# Sch6.net
KiCad netlist of a schematic drawn in EAGLE
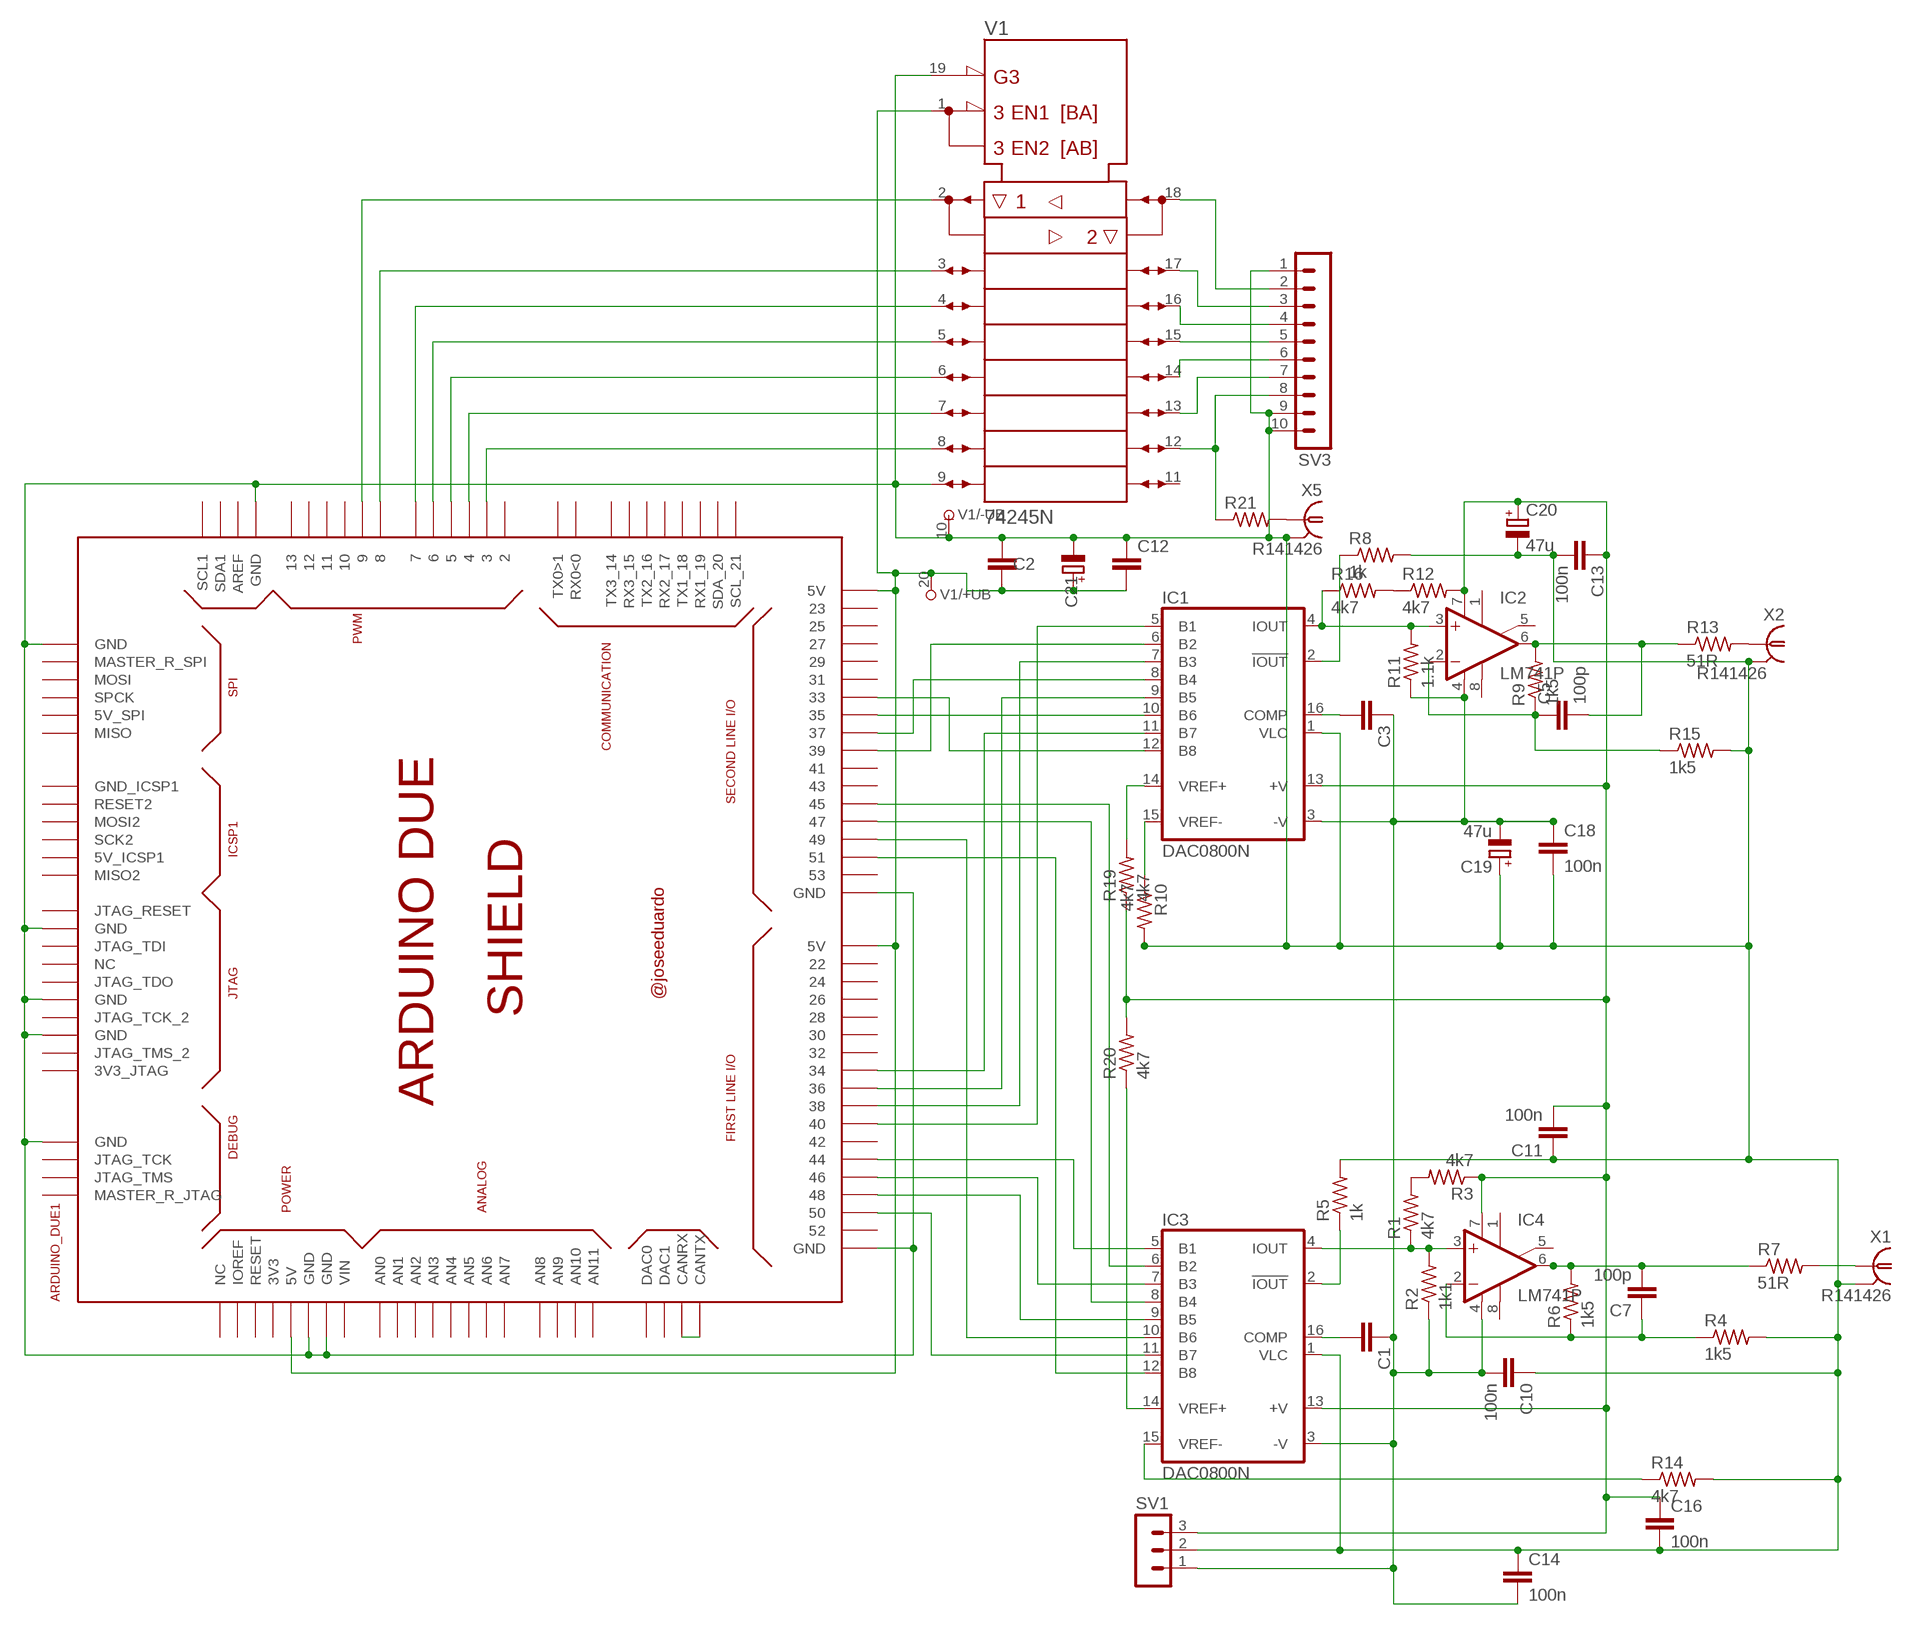
[diagram p0: schematic, sheet 1]

(export (version "E")
  (design (tool "Eeschema 10.0.6"))
  (components
    (comp (ref "ARDUINO_DUE1")
      (value "ARDUINO_DUE_SHIELD")
      (footprint "eagle-import:ARDUINO_DUE_SHIELD")
      (libsource (lib "eagle-import") (part "ARDUINO_DUE_SHIELD"))
    )
    (comp (ref "C1")
      (value "C-EU050-025X075")
      (footprint "eagle-import:C050-025X075")
      (libsource (lib "eagle-import") (part "C-EU050-025X075"))
    )
    (comp (ref "C2")
      (value "C-EU050-025X075")
      (footprint "eagle-import:C050-025X075")
      (libsource (lib "eagle-import") (part "C-EU050-025X075"))
    )
    (comp (ref "C3")
      (value "C-EU050-025X075")
      (footprint "eagle-import:C050-025X075")
      (libsource (lib "eagle-import") (part "C-EU050-025X075"))
    )
    (comp (ref "C5")
      (value "100p")
      (footprint "eagle-import:C050-025X075")
      (libsource (lib "eagle-import") (part "C-EU050-025X075"))
    )
    (comp (ref "C7")
      (value "100p")
      (footprint "eagle-import:C050-025X075")
      (libsource (lib "eagle-import") (part "C-EU050-025X075"))
    )
    (comp (ref "C10")
      (value "100n")
      (footprint "eagle-import:C050-025X075")
      (libsource (lib "eagle-import") (part "C-EU050-025X075"))
    )
    (comp (ref "C11")
      (value "100n")
      (footprint "eagle-import:C050-025X075")
      (libsource (lib "eagle-import") (part "C-EU050-025X075"))
    )
    (comp (ref "C12")
      (value "C-EU050-025X075")
      (footprint "eagle-import:C050-025X075")
      (libsource (lib "eagle-import") (part "C-EU050-025X075"))
    )
    (comp (ref "C13")
      (value "100n")
      (footprint "eagle-import:C050-025X075")
      (libsource (lib "eagle-import") (part "C-EU050-025X075"))
    )
    (comp (ref "C14")
      (value "100n")
      (footprint "eagle-import:C050-025X075")
      (libsource (lib "eagle-import") (part "C-EU050-025X075"))
    )
    (comp (ref "C16")
      (value "100n")
      (footprint "eagle-import:C050-025X075")
      (libsource (lib "eagle-import") (part "C-EU050-025X075"))
    )
    (comp (ref "C18")
      (value "100n")
      (footprint "eagle-import:C050-025X075")
      (libsource (lib "eagle-import") (part "C-EU050-025X075"))
    )
    (comp (ref "C19")
      (value "47u")
      (footprint "eagle-import:E5-10,5")
      (libsource (lib "eagle-import") (part "CPOL-EUE5-10.5"))
    )
    (comp (ref "C20")
      (value "47u")
      (footprint "eagle-import:E5-10,5")
      (libsource (lib "eagle-import") (part "CPOL-EUE5-10.5"))
    )
    (comp (ref "C21")
      (value "CPOL-EUE5-10.5")
      (footprint "eagle-import:E5-10,5")
      (libsource (lib "eagle-import") (part "CPOL-EUE5-10.5"))
    )
    (comp (ref "IC1")
      (value "DAC0800N")
      (footprint "eagle-import:DIL16")
      (libsource (lib "eagle-import") (part "DAC0800N"))
    )
    (comp (ref "IC2")
      (value "LM741P")
      (footprint "eagle-import:DIL08")
      (libsource (lib "eagle-import") (part "741PLM"))
    )
    (comp (ref "IC3")
      (value "DAC0800N")
      (footprint "eagle-import:DIL16")
      (libsource (lib "eagle-import") (part "DAC0800N"))
    )
    (comp (ref "IC4")
      (value "LM741P")
      (footprint "eagle-import:DIL08")
      (libsource (lib "eagle-import") (part "741PLM"))
    )
    (comp (ref "R1")
      (value "4k7")
      (footprint "eagle-import:0207_10")
      (libsource (lib "eagle-import") (part "R-US_0207/10"))
    )
    (comp (ref "R2")
      (value "1k1")
      (footprint "eagle-import:0207_10")
      (libsource (lib "eagle-import") (part "R-US_0207/10"))
    )
    (comp (ref "R3")
      (value "4k7")
      (footprint "eagle-import:0207_10")
      (libsource (lib "eagle-import") (part "R-US_0207/10"))
    )
    (comp (ref "R4")
      (value "1k5")
      (footprint "eagle-import:0207_10")
      (libsource (lib "eagle-import") (part "R-US_0207/10"))
    )
    (comp (ref "R5")
      (value "1k")
      (footprint "eagle-import:0207_10")
      (libsource (lib "eagle-import") (part "R-US_0207/10"))
    )
    (comp (ref "R6")
      (value "1k5")
      (footprint "eagle-import:0207_10")
      (libsource (lib "eagle-import") (part "R-US_0207/10"))
    )
    (comp (ref "R7")
      (value "51R")
      (footprint "eagle-import:0207_10")
      (libsource (lib "eagle-import") (part "R-US_0207/10"))
    )
    (comp (ref "R8")
      (value "1k")
      (footprint "eagle-import:0207_10")
      (libsource (lib "eagle-import") (part "R-US_0207/10"))
    )
    (comp (ref "R9")
      (value "1k5")
      (footprint "eagle-import:0207_10")
      (libsource (lib "eagle-import") (part "R-US_0207/10"))
    )
    (comp (ref "R10")
      (value "4k7")
      (footprint "eagle-import:0207_10")
      (libsource (lib "eagle-import") (part "R-US_0207/10"))
    )
    (comp (ref "R11")
      (value "1.1k")
      (footprint "eagle-import:0207_10")
      (libsource (lib "eagle-import") (part "R-US_0207/10"))
    )
    (comp (ref "R12")
      (value "4k7")
      (footprint "eagle-import:0207_10")
      (libsource (lib "eagle-import") (part "R-US_0207/10"))
    )
    (comp (ref "R13")
      (value "51R")
      (footprint "eagle-import:0207_10")
      (libsource (lib "eagle-import") (part "R-US_0207/10"))
    )
    (comp (ref "R14")
      (value "4k7")
      (footprint "eagle-import:0207_10")
      (libsource (lib "eagle-import") (part "R-US_0207/10"))
    )
    (comp (ref "R15")
      (value "1k5")
      (footprint "eagle-import:0207_10")
      (libsource (lib "eagle-import") (part "R-US_0207/10"))
    )
    (comp (ref "R16")
      (value "4k7")
      (footprint "eagle-import:0207_10")
      (libsource (lib "eagle-import") (part "R-US_0207/10"))
    )
    (comp (ref "R19")
      (value "4k7")
      (footprint "eagle-import:0207_10")
      (libsource (lib "eagle-import") (part "R-US_0207/10"))
    )
    (comp (ref "R20")
      (value "4k7")
      (footprint "eagle-import:0207_10")
      (libsource (lib "eagle-import") (part "R-US_0207/10"))
    )
    (comp (ref "R21")
      (value "R-US_0207/10")
      (footprint "eagle-import:0207_10")
      (libsource (lib "eagle-import") (part "R-US_0207/10"))
    )
    (comp (ref "SV1")
      (value "MA03-1")
      (footprint "eagle-import:MA03-1")
      (libsource (lib "eagle-import") (part "MA03-1"))
    )
    (comp (ref "SV3")
      (value "MA10-1")
      (footprint "eagle-import:MA10-1")
      (libsource (lib "eagle-import") (part "MA10-1"))
    )
    (comp (ref "V1")
      (value "74245N")
      (footprint "eagle-import:DIL20")
      (libsource (lib "eagle-import") (part "74245N"))
    )
    (comp (ref "X1")
      (value "R141426")
      (footprint "eagle-import:R141426")
      (fields (field (name "MF") "FARNELL") (field (name "MPN") "R141426161"))
      (libsource (lib "eagle-import") (part "R141426"))
    )
    (comp (ref "X2")
      (value "R141426")
      (footprint "eagle-import:R141426")
      (fields (field (name "MF") "FARNELL") (field (name "MPN") "R141426161"))
      (libsource (lib "eagle-import") (part "R141426"))
    )
    (comp (ref "X5")
      (value "R141426")
      (footprint "eagle-import:R141426")
      (fields (field (name "MF") "FARNELL") (field (name "MPN") "R141426161"))
      (libsource (lib "eagle-import") (part "R141426"))
    )
  )
  (nets
    (net (code "1") (name "Net-(ARDUINO_DUE1-PadCANRX)") (class "Default")
      (node (ref "ARDUINO_DUE1") (pin "CANRX") (pinfunction "CANRX_CANRX") (pintype "bidirectional"))
      (node (ref "ARDUINO_DUE1") (pin "CANTX") (pinfunction "CANTX_CANTX") (pintype "bidirectional"))
    )
    (net (code "2") (name "Net-(IC1-+V)") (class "Default")
      (node (ref "C11") (pin "2") (pinfunction "2_2") (pintype "passive"))
      (node (ref "C13") (pin "1") (pinfunction "1_1") (pintype "passive"))
      (node (ref "C16") (pin "1") (pinfunction "1_1") (pintype "passive"))
      (node (ref "C20") (pin "+") (pinfunction "+_+") (pintype "passive"))
      (node (ref "IC1") (pin "13") (pinfunction "+V_13") (pintype "power_in"))
      (node (ref "IC2") (pin "7") (pinfunction "V+_7") (pintype "power_in"))
      (node (ref "IC3") (pin "13") (pinfunction "+V_13") (pintype "power_in"))
      (node (ref "IC4") (pin "7") (pinfunction "V+_7") (pintype "power_in"))
      (node (ref "R12") (pin "2") (pinfunction "2_2") (pintype "passive"))
      (node (ref "R19") (pin "1") (pinfunction "1_1") (pintype "passive"))
      (node (ref "R20") (pin "2") (pinfunction "2_2") (pintype "passive"))
      (node (ref "R3") (pin "1") (pinfunction "1_1") (pintype "passive"))
      (node (ref "SV1") (pin "3") (pinfunction "3_3") (pintype "passive"))
    )
    (net (code "3") (name "Net-(IC1--V)") (class "Default")
      (node (ref "C1") (pin "1") (pinfunction "1_1") (pintype "passive"))
      (node (ref "C10") (pin "2") (pinfunction "2_2") (pintype "passive"))
      (node (ref "C14") (pin "2") (pinfunction "2_2") (pintype "passive"))
      (node (ref "C18") (pin "1") (pinfunction "1_1") (pintype "passive"))
      (node (ref "C19") (pin "-") (pinfunction "-_-") (pintype "passive"))
      (node (ref "C3") (pin "1") (pinfunction "1_1") (pintype "passive"))
      (node (ref "IC1") (pin "3") (pinfunction "-V_3") (pintype "power_in"))
      (node (ref "IC2") (pin "4") (pinfunction "V-_4") (pintype "power_in"))
      (node (ref "IC3") (pin "3") (pinfunction "-V_3") (pintype "power_in"))
      (node (ref "IC4") (pin "4") (pinfunction "V-_4") (pintype "power_in"))
      (node (ref "R11") (pin "1") (pinfunction "1_1") (pintype "passive"))
      (node (ref "R2") (pin "1") (pinfunction "1_1") (pintype "passive"))
      (node (ref "SV1") (pin "1") (pinfunction "1_1") (pintype "passive"))
    )
    (net (code "4") (name "Net-(IC1-B1)") (class "Default")
      (node (ref "ARDUINO_DUE1") (pin "40") (pinfunction "40_40") (pintype "bidirectional"))
      (node (ref "IC1") (pin "5") (pinfunction "B1_5") (pintype "input"))
    )
    (net (code "5") (name "Net-(IC1-B2)") (class "Default")
      (node (ref "ARDUINO_DUE1") (pin "39") (pinfunction "39_39") (pintype "bidirectional"))
      (node (ref "IC1") (pin "6") (pinfunction "B2_6") (pintype "input"))
    )
    (net (code "6") (name "Net-(IC1-B3)") (class "Default")
      (node (ref "ARDUINO_DUE1") (pin "38") (pinfunction "38_38") (pintype "bidirectional"))
      (node (ref "IC1") (pin "7") (pinfunction "B3_7") (pintype "input"))
    )
    (net (code "7") (name "Net-(IC1-B4)") (class "Default")
      (node (ref "ARDUINO_DUE1") (pin "37") (pinfunction "37_37") (pintype "bidirectional"))
      (node (ref "IC1") (pin "8") (pinfunction "B4_8") (pintype "input"))
    )
    (net (code "8") (name "Net-(IC1-B5)") (class "Default")
      (node (ref "ARDUINO_DUE1") (pin "36") (pinfunction "36_36") (pintype "bidirectional"))
      (node (ref "IC1") (pin "9") (pinfunction "B5_9") (pintype "input"))
    )
    (net (code "9") (name "Net-(IC1-B6)") (class "Default")
      (node (ref "ARDUINO_DUE1") (pin "35") (pinfunction "35_35") (pintype "bidirectional"))
      (node (ref "IC1") (pin "10") (pinfunction "B6_10") (pintype "input"))
    )
    (net (code "10") (name "Net-(IC1-B7)") (class "Default")
      (node (ref "ARDUINO_DUE1") (pin "34") (pinfunction "34_34") (pintype "bidirectional"))
      (node (ref "IC1") (pin "11") (pinfunction "B7_11") (pintype "input"))
    )
    (net (code "11") (name "Net-(IC1-B8)") (class "Default")
      (node (ref "ARDUINO_DUE1") (pin "33") (pinfunction "33_33") (pintype "bidirectional"))
      (node (ref "IC1") (pin "12") (pinfunction "B8_12") (pintype "input"))
    )
    (net (code "12") (name "Net-(IC1-COMP)") (class "Default")
      (node (ref "C3") (pin "2") (pinfunction "2_2") (pintype "passive"))
      (node (ref "IC1") (pin "16") (pinfunction "COMP_16") (pintype "input"))
    )
    (net (code "13") (name "Net-(IC1-IOUT)") (class "Default")
      (node (ref "IC1") (pin "4") (pinfunction "IOUT_4") (pintype "output"))
      (node (ref "IC2") (pin "3") (pinfunction "+IN_3") (pintype "input"))
      (node (ref "R11") (pin "2") (pinfunction "2_2") (pintype "passive"))
      (node (ref "R16") (pin "1") (pinfunction "1_1") (pintype "passive"))
    )
    (net (code "14") (name "Net-(IC1-VLC)") (class "Default")
      (node (ref "ARDUINO_DUE1") (pin "GND") (pinfunction "GND_GND") (pintype "bidirectional"))
      (node (ref "ARDUINO_DUE1") (pin "GND_1") (pinfunction "GND_GND_1") (pintype "bidirectional"))
      (node (ref "ARDUINO_DUE1") (pin "GND_10") (pinfunction "GND_GND_10") (pintype "bidirectional"))
      (node (ref "ARDUINO_DUE1") (pin "GND_2") (pinfunction "GND_GND_2") (pintype "bidirectional"))
      (node (ref "ARDUINO_DUE1") (pin "GND_3") (pinfunction "GND_GND_3") (pintype "bidirectional"))
      (node (ref "ARDUINO_DUE1") (pin "GND_4") (pinfunction "GND_GND_4") (pintype "bidirectional"))
      (node (ref "ARDUINO_DUE1") (pin "GND_5") (pinfunction "GND_GND_5") (pintype "bidirectional"))
      (node (ref "ARDUINO_DUE1") (pin "GND_7") (pinfunction "GND_GND_7") (pintype "bidirectional"))
      (node (ref "ARDUINO_DUE1") (pin "GND_8") (pinfunction "GND_GND_8") (pintype "bidirectional"))
      (node (ref "ARDUINO_DUE1") (pin "GND_9") (pinfunction "GND_GND_9") (pintype "bidirectional"))
      (node (ref "C10") (pin "1") (pinfunction "1_1") (pintype "passive"))
      (node (ref "C11") (pin "1") (pinfunction "1_1") (pintype "passive"))
      (node (ref "C12") (pin "1") (pinfunction "1_1") (pintype "passive"))
      (node (ref "C13") (pin "2") (pinfunction "2_2") (pintype "passive"))
      (node (ref "C14") (pin "1") (pinfunction "1_1") (pintype "passive"))
      (node (ref "C16") (pin "2") (pinfunction "2_2") (pintype "passive"))
      (node (ref "C18") (pin "2") (pinfunction "2_2") (pintype "passive"))
      (node (ref "C19") (pin "+") (pinfunction "+_+") (pintype "passive"))
      (node (ref "C2") (pin "1") (pinfunction "1_1") (pintype "passive"))
      (node (ref "C20") (pin "-") (pinfunction "-_-") (pintype "passive"))
      (node (ref "C21") (pin "-") (pinfunction "-_-") (pintype "passive"))
      (node (ref "IC1") (pin "1") (pinfunction "VLC_1") (pintype "input"))
      (node (ref "IC3") (pin "1") (pinfunction "VLC_1") (pintype "input"))
      (node (ref "R10") (pin "2") (pinfunction "2_2") (pintype "passive"))
      (node (ref "R14") (pin "2") (pinfunction "2_2") (pintype "passive"))
      (node (ref "R15") (pin "2") (pinfunction "2_2") (pintype "passive"))
      (node (ref "R4") (pin "2") (pinfunction "2_2") (pintype "passive"))
      (node (ref "R5") (pin "2") (pinfunction "2_2") (pintype "passive"))
      (node (ref "R8") (pin "2") (pinfunction "2_2") (pintype "passive"))
      (node (ref "SV1") (pin "2") (pinfunction "2_2") (pintype "passive"))
      (node (ref "SV3") (pin "1") (pinfunction "1_1") (pintype "passive"))
      (node (ref "SV3") (pin "10") (pinfunction "10_10") (pintype "passive"))
      (node (ref "SV3") (pin "9") (pinfunction "9_9") (pintype "passive"))
      (node (ref "V1") (pin "10") (pinfunction "-UB_10") (pintype "power_in"))
      (node (ref "V1") (pin "19") (pinfunction "~{G}_19") (pintype "input"))
      (node (ref "V1") (pin "9") (pinfunction "A8_9") (pintype "bidirectional"))
      (node (ref "X1") (pin "2") (pinfunction "2_2") (pintype "passive"))
      (node (ref "X1") (pin "3") (pinfunction "2_3") (pintype "passive"))
      (node (ref "X1") (pin "4") (pinfunction "2_4") (pintype "passive"))
      (node (ref "X1") (pin "5") (pinfunction "2_5") (pintype "passive"))
      (node (ref "X2") (pin "2") (pinfunction "2_2") (pintype "passive"))
      (node (ref "X2") (pin "3") (pinfunction "2_3") (pintype "passive"))
      (node (ref "X2") (pin "4") (pinfunction "2_4") (pintype "passive"))
      (node (ref "X2") (pin "5") (pinfunction "2_5") (pintype "passive"))
      (node (ref "X5") (pin "2") (pinfunction "2_2") (pintype "passive"))
      (node (ref "X5") (pin "3") (pinfunction "2_3") (pintype "passive"))
      (node (ref "X5") (pin "4") (pinfunction "2_4") (pintype "passive"))
      (node (ref "X5") (pin "5") (pinfunction "2_5") (pintype "passive"))
    )
    (net (code "15") (name "Net-(IC1-VREF+)") (class "Default")
      (node (ref "IC1") (pin "14") (pinfunction "VREF+_14") (pintype "input"))
      (node (ref "R19") (pin "2") (pinfunction "2_2") (pintype "passive"))
    )
    (net (code "16") (name "Net-(IC1-VREF-)") (class "Default")
      (node (ref "IC1") (pin "15") (pinfunction "VREF-_15") (pintype "input"))
      (node (ref "R10") (pin "1") (pinfunction "1_1") (pintype "passive"))
    )
    (net (code "17") (name "Net-(IC1-~{IOUT})") (class "Default")
      (node (ref "IC1") (pin "2") (pinfunction "~{IOUT}_2") (pintype "output"))
      (node (ref "R8") (pin "1") (pinfunction "1_1") (pintype "passive"))
    )
    (net (code "18") (name "Net-(IC2--IN)") (class "Default")
      (node (ref "C5") (pin "1") (pinfunction "1_1") (pintype "passive"))
      (node (ref "IC2") (pin "2") (pinfunction "-IN_2") (pintype "input"))
      (node (ref "R15") (pin "1") (pinfunction "1_1") (pintype "passive"))
      (node (ref "R9") (pin "1") (pinfunction "1_1") (pintype "passive"))
    )
    (net (code "19") (name "Net-(IC2-OUT)") (class "Default")
      (node (ref "C5") (pin "2") (pinfunction "2_2") (pintype "passive"))
      (node (ref "IC2") (pin "6") (pinfunction "OUT_6") (pintype "output"))
      (node (ref "R13") (pin "1") (pinfunction "1_1") (pintype "passive"))
      (node (ref "R9") (pin "2") (pinfunction "2_2") (pintype "passive"))
    )
    (net (code "20") (name "Net-(IC3-B1)") (class "Default")
      (node (ref "ARDUINO_DUE1") (pin "44") (pinfunction "44_44") (pintype "bidirectional"))
      (node (ref "IC3") (pin "5") (pinfunction "B1_5") (pintype "input"))
    )
    (net (code "21") (name "Net-(IC3-B2)") (class "Default")
      (node (ref "ARDUINO_DUE1") (pin "45") (pinfunction "45_45") (pintype "bidirectional"))
      (node (ref "IC3") (pin "6") (pinfunction "B2_6") (pintype "input"))
    )
    (net (code "22") (name "Net-(IC3-B3)") (class "Default")
      (node (ref "ARDUINO_DUE1") (pin "46") (pinfunction "46_46") (pintype "bidirectional"))
      (node (ref "IC3") (pin "7") (pinfunction "B3_7") (pintype "input"))
    )
    (net (code "23") (name "Net-(IC3-B4)") (class "Default")
      (node (ref "ARDUINO_DUE1") (pin "47") (pinfunction "47_47") (pintype "bidirectional"))
      (node (ref "IC3") (pin "8") (pinfunction "B4_8") (pintype "input"))
    )
    (net (code "24") (name "Net-(IC3-B5)") (class "Default")
      (node (ref "ARDUINO_DUE1") (pin "48") (pinfunction "48_48") (pintype "bidirectional"))
      (node (ref "IC3") (pin "9") (pinfunction "B5_9") (pintype "input"))
    )
    (net (code "25") (name "Net-(IC3-B6)") (class "Default")
      (node (ref "ARDUINO_DUE1") (pin "49") (pinfunction "49_49") (pintype "bidirectional"))
      (node (ref "IC3") (pin "10") (pinfunction "B6_10") (pintype "input"))
    )
    (net (code "26") (name "Net-(IC3-B7)") (class "Default")
      (node (ref "ARDUINO_DUE1") (pin "50") (pinfunction "50_50") (pintype "bidirectional"))
      (node (ref "IC3") (pin "11") (pinfunction "B7_11") (pintype "input"))
    )
    (net (code "27") (name "Net-(IC3-B8)") (class "Default")
      (node (ref "ARDUINO_DUE1") (pin "51") (pinfunction "51_51") (pintype "bidirectional"))
      (node (ref "IC3") (pin "12") (pinfunction "B8_12") (pintype "input"))
    )
    (net (code "28") (name "Net-(IC3-COMP)") (class "Default")
      (node (ref "C1") (pin "2") (pinfunction "2_2") (pintype "passive"))
      (node (ref "IC3") (pin "16") (pinfunction "COMP_16") (pintype "input"))
    )
    (net (code "29") (name "Net-(IC3-IOUT)") (class "Default")
      (node (ref "IC3") (pin "4") (pinfunction "IOUT_4") (pintype "output"))
      (node (ref "IC4") (pin "3") (pinfunction "+IN_3") (pintype "input"))
      (node (ref "R1") (pin "1") (pinfunction "1_1") (pintype "passive"))
      (node (ref "R2") (pin "2") (pinfunction "2_2") (pintype "passive"))
    )
    (net (code "30") (name "Net-(IC3-VREF+)") (class "Default")
      (node (ref "IC3") (pin "14") (pinfunction "VREF+_14") (pintype "input"))
      (node (ref "R20") (pin "1") (pinfunction "1_1") (pintype "passive"))
    )
    (net (code "31") (name "Net-(IC3-VREF-)") (class "Default")
      (node (ref "IC3") (pin "15") (pinfunction "VREF-_15") (pintype "input"))
      (node (ref "R14") (pin "1") (pinfunction "1_1") (pintype "passive"))
    )
    (net (code "32") (name "Net-(IC3-~{IOUT})") (class "Default")
      (node (ref "IC3") (pin "2") (pinfunction "~{IOUT}_2") (pintype "output"))
      (node (ref "R5") (pin "1") (pinfunction "1_1") (pintype "passive"))
    )
    (net (code "33") (name "Net-(IC4--IN)") (class "Default")
      (node (ref "C7") (pin "1") (pinfunction "1_1") (pintype "passive"))
      (node (ref "IC4") (pin "2") (pinfunction "-IN_2") (pintype "input"))
      (node (ref "R4") (pin "1") (pinfunction "1_1") (pintype "passive"))
      (node (ref "R6") (pin "1") (pinfunction "1_1") (pintype "passive"))
    )
    (net (code "34") (name "Net-(IC4-OUT)") (class "Default")
      (node (ref "C7") (pin "2") (pinfunction "2_2") (pintype "passive"))
      (node (ref "IC4") (pin "6") (pinfunction "OUT_6") (pintype "output"))
      (node (ref "R6") (pin "2") (pinfunction "2_2") (pintype "passive"))
      (node (ref "R7") (pin "1") (pinfunction "1_1") (pintype "passive"))
    )
    (net (code "35") (name "Net-(R1-Pad2)") (class "Default")
      (node (ref "R1") (pin "2") (pinfunction "2_2") (pintype "passive"))
      (node (ref "R3") (pin "2") (pinfunction "2_2") (pintype "passive"))
    )
    (net (code "36") (name "Net-(R7-Pad2)") (class "Default")
      (node (ref "R7") (pin "2") (pinfunction "2_2") (pintype "passive"))
      (node (ref "X1") (pin "1") (pinfunction "1_1") (pintype "passive"))
    )
    (net (code "37") (name "Net-(R12-Pad1)") (class "Default")
      (node (ref "R12") (pin "1") (pinfunction "1_1") (pintype "passive"))
      (node (ref "R16") (pin "2") (pinfunction "2_2") (pintype "passive"))
    )
    (net (code "38") (name "Net-(R13-Pad2)") (class "Default")
      (node (ref "R13") (pin "2") (pinfunction "2_2") (pintype "passive"))
      (node (ref "X2") (pin "1") (pinfunction "1_1") (pintype "passive"))
    )
    (net (code "39") (name "Net-(R21-Pad2)") (class "Default")
      (node (ref "R21") (pin "2") (pinfunction "2_2") (pintype "passive"))
      (node (ref "X5") (pin "1") (pinfunction "1_1") (pintype "passive"))
    )
    (net (code "40") (name "Net-(V1A-+UB)") (class "Default")
      (node (ref "ARDUINO_DUE1") (pin "5V0") (pinfunction "5V_5V0") (pintype "bidirectional"))
      (node (ref "ARDUINO_DUE1") (pin "5V0_1") (pinfunction "5V_5V0_1") (pintype "bidirectional"))
      (node (ref "ARDUINO_DUE1") (pin "5V0_2") (pinfunction "5V_5V0_2") (pintype "bidirectional"))
      (node (ref "C12") (pin "2") (pinfunction "2_2") (pintype "passive"))
      (node (ref "C2") (pin "2") (pinfunction "2_2") (pintype "passive"))
      (node (ref "C21") (pin "+") (pinfunction "+_+") (pintype "passive"))
      (node (ref "V1") (pin "1") (pinfunction "DIR_1") (pintype "input"))
      (node (ref "V1") (pin "20") (pinfunction "+UB_20") (pintype "power_in"))
    )
    (net (code "41") (name "Net-(V1C-A1)") (class "Default")
      (node (ref "ARDUINO_DUE1") (pin "9") (pinfunction "9_9") (pintype "bidirectional"))
      (node (ref "V1") (pin "2") (pinfunction "A1_2") (pintype "bidirectional"))
    )
    (net (code "42") (name "Net-(V1C-A2)") (class "Default")
      (node (ref "ARDUINO_DUE1") (pin "8") (pinfunction "8_8") (pintype "bidirectional"))
      (node (ref "V1") (pin "3") (pinfunction "A2_3") (pintype "bidirectional"))
    )
    (net (code "43") (name "Net-(V1C-A3)") (class "Default")
      (node (ref "ARDUINO_DUE1") (pin "7") (pinfunction "7_7") (pintype "bidirectional"))
      (node (ref "V1") (pin "4") (pinfunction "A3_4") (pintype "bidirectional"))
    )
    (net (code "44") (name "Net-(V1C-A4)") (class "Default")
      (node (ref "ARDUINO_DUE1") (pin "6") (pinfunction "6_6") (pintype "bidirectional"))
      (node (ref "V1") (pin "5") (pinfunction "A4_5") (pintype "bidirectional"))
    )
    (net (code "45") (name "Net-(V1C-A5)") (class "Default")
      (node (ref "ARDUINO_DUE1") (pin "5") (pinfunction "5_5") (pintype "bidirectional"))
      (node (ref "V1") (pin "6") (pinfunction "A5_6") (pintype "bidirectional"))
    )
    (net (code "46") (name "Net-(V1C-A6)") (class "Default")
      (node (ref "ARDUINO_DUE1") (pin "4") (pinfunction "4_4") (pintype "bidirectional"))
      (node (ref "V1") (pin "7") (pinfunction "A6_7") (pintype "bidirectional"))
    )
    (net (code "47") (name "Net-(V1C-A7)") (class "Default")
      (node (ref "ARDUINO_DUE1") (pin "3") (pinfunction "3_3") (pintype "bidirectional"))
      (node (ref "V1") (pin "8") (pinfunction "A7_8") (pintype "bidirectional"))
    )
    (net (code "48") (name "Net-(V1C-B1)") (class "Default")
      (node (ref "SV3") (pin "2") (pinfunction "2_2") (pintype "passive"))
      (node (ref "V1") (pin "18") (pinfunction "B1_18") (pintype "bidirectional"))
    )
    (net (code "49") (name "Net-(V1C-B2)") (class "Default")
      (node (ref "SV3") (pin "3") (pinfunction "3_3") (pintype "passive"))
      (node (ref "V1") (pin "17") (pinfunction "B2_17") (pintype "bidirectional"))
    )
    (net (code "50") (name "Net-(V1C-B3)") (class "Default")
      (node (ref "SV3") (pin "4") (pinfunction "4_4") (pintype "passive"))
      (node (ref "V1") (pin "16") (pinfunction "B3_16") (pintype "bidirectional"))
    )
    (net (code "51") (name "Net-(V1C-B4)") (class "Default")
      (node (ref "SV3") (pin "5") (pinfunction "5_5") (pintype "passive"))
      (node (ref "V1") (pin "15") (pinfunction "B4_15") (pintype "bidirectional"))
    )
    (net (code "52") (name "Net-(V1C-B5)") (class "Default")
      (node (ref "SV3") (pin "6") (pinfunction "6_6") (pintype "passive"))
      (node (ref "V1") (pin "14") (pinfunction "B5_14") (pintype "bidirectional"))
    )
    (net (code "53") (name "Net-(V1C-B6)") (class "Default")
      (node (ref "SV3") (pin "7") (pinfunction "7_7") (pintype "passive"))
      (node (ref "V1") (pin "13") (pinfunction "B6_13") (pintype "bidirectional"))
    )
    (net (code "54") (name "Net-(V1C-B7)") (class "Default")
      (node (ref "R21") (pin "1") (pinfunction "1_1") (pintype "passive"))
      (node (ref "SV3") (pin "8") (pinfunction "8_8") (pintype "passive"))
      (node (ref "V1") (pin "12") (pinfunction "B7_12") (pintype "bidirectional"))
    )
    (net (code "55") (name "unconnected-(ARDUINO_DUE1-5V_SPI-Pad5V_2)") (class "Default")
      (node (ref "ARDUINO_DUE1") (pin "5V_2") (pinfunction "5V_SPI_5V_2") (pintype "bidirectional"))
    )
    (net (code "56") (name "unconnected-(ARDUINO_DUE1-AN0-PadA0)") (class "Default")
      (node (ref "ARDUINO_DUE1") (pin "A0") (pinfunction "AN0_A0") (pintype "bidirectional"))
    )
    (net (code "57") (name "unconnected-(ARDUINO_DUE1-AN1-PadA1)") (class "Default")
      (node (ref "ARDUINO_DUE1") (pin "A1") (pinfunction "AN1_A1") (pintype "bidirectional"))
    )
    (net (code "58") (name "unconnected-(ARDUINO_DUE1-AN2-PadA2)") (class "Default")
      (node (ref "ARDUINO_DUE1") (pin "A2") (pinfunction "AN2_A2") (pintype "bidirectional"))
    )
    (net (code "59") (name "unconnected-(ARDUINO_DUE1-AN3-PadA3)") (class "Default")
      (node (ref "ARDUINO_DUE1") (pin "A3") (pinfunction "AN3_A3") (pintype "bidirectional"))
    )
    (net (code "60") (name "unconnected-(ARDUINO_DUE1-AN4-PadA4)") (class "Default")
      (node (ref "ARDUINO_DUE1") (pin "A4") (pinfunction "AN4_A4") (pintype "bidirectional"))
    )
    (net (code "61") (name "unconnected-(ARDUINO_DUE1-AN5-PadA5)") (class "Default")
      (node (ref "ARDUINO_DUE1") (pin "A5") (pinfunction "AN5_A5") (pintype "bidirectional"))
    )
    (net (code "62") (name "unconnected-(ARDUINO_DUE1-AN6-PadA6)") (class "Default")
      (node (ref "ARDUINO_DUE1") (pin "A6") (pinfunction "AN6_A6") (pintype "bidirectional"))
    )
    (net (code "63") (name "unconnected-(ARDUINO_DUE1-AN7-PadA7)") (class "Default")
      (node (ref "ARDUINO_DUE1") (pin "A7") (pinfunction "AN7_A7") (pintype "bidirectional"))
    )
    (net (code "64") (name "unconnected-(ARDUINO_DUE1-AN8-PadA8)") (class "Default")
      (node (ref "ARDUINO_DUE1") (pin "A8") (pinfunction "AN8_A8") (pintype "bidirectional"))
    )
    (net (code "65") (name "unconnected-(ARDUINO_DUE1-AN9-PadA9)") (class "Default")
      (node (ref "ARDUINO_DUE1") (pin "A9") (pinfunction "AN9_A9") (pintype "bidirectional"))
    )
    (net (code "66") (name "unconnected-(ARDUINO_DUE1-AN10-PadA10)") (class "Default")
      (node (ref "ARDUINO_DUE1") (pin "A10") (pinfunction "AN10_A10") (pintype "bidirectional"))
    )
    (net (code "67") (name "unconnected-(ARDUINO_DUE1-AN11-PadA11)") (class "Default")
      (node (ref "ARDUINO_DUE1") (pin "A11") (pinfunction "AN11_A11") (pintype "bidirectional"))
    )
    (net (code "68") (name "unconnected-(ARDUINO_DUE1-MASTER_R_JTAG-PadMASTER_RESET_JTAG)") (class "Default")
      (node (ref "ARDUINO_DUE1") (pin "MASTER_RESET_JTAG") (pinfunction "MASTER_R_JTAG_MASTER_RESET_JTAG") (pintype "bidirectional"))
    )
    (net (code "69") (name "unconnected-(ARDUINO_DUE1-MASTER_R_SPI-PadMASTER_RESET_SPI)") (class "Default")
      (node (ref "ARDUINO_DUE1") (pin "MASTER_RESET_SPI") (pinfunction "MASTER_R_SPI_MASTER_RESET_SPI") (pintype "bidirectional"))
    )
    (net (code "70") (name "unconnected-(ARDUINO_DUE1-NC-PadNC_2)") (class "Default")
      (node (ref "ARDUINO_DUE1") (pin "NC_2") (pinfunction "NC_NC_2") (pintype "no_connect"))
    )
    (net (code "71") (name "unconnected-(ARDUINO_DUE1-NC-PadNC_5)") (class "Default")
      (node (ref "ARDUINO_DUE1") (pin "NC_5") (pinfunction "NC_NC_5") (pintype "bidirectional"))
    )
    (net (code "72") (name "unconnected-(ARDUINO_DUE1-Pad2)") (class "Default")
      (node (ref "ARDUINO_DUE1") (pin "2") (pinfunction "2_2") (pintype "bidirectional"))
    )
    (net (code "73") (name "unconnected-(ARDUINO_DUE1-Pad3V3)") (class "Default")
      (node (ref "ARDUINO_DUE1") (pin "3V3") (pinfunction "3V3_3V3") (pintype "bidirectional"))
    )
    (net (code "74") (name "unconnected-(ARDUINO_DUE1-Pad3V3_JTAG)") (class "Default")
      (node (ref "ARDUINO_DUE1") (pin "3V3_JTAG") (pinfunction "3V3_JTAG_3V3_JTAG") (pintype "bidirectional"))
    )
    (net (code "75") (name "unconnected-(ARDUINO_DUE1-Pad5V_ICSP1)") (class "Default")
      (node (ref "ARDUINO_DUE1") (pin "5V_ICSP1") (pinfunction "5V_ICSP1_5V_ICSP1") (pintype "bidirectional"))
    )
    (net (code "76") (name "unconnected-(ARDUINO_DUE1-Pad10)") (class "Default")
      (node (ref "ARDUINO_DUE1") (pin "10") (pinfunction "10_10") (pintype "bidirectional"))
    )
    (net (code "77") (name "unconnected-(ARDUINO_DUE1-Pad11)") (class "Default")
      (node (ref "ARDUINO_DUE1") (pin "11") (pinfunction "11_11") (pintype "bidirectional"))
    )
    (net (code "78") (name "unconnected-(ARDUINO_DUE1-Pad12)") (class "Default")
      (node (ref "ARDUINO_DUE1") (pin "12") (pinfunction "12_12") (pintype "bidirectional"))
    )
    (net (code "79") (name "unconnected-(ARDUINO_DUE1-Pad13)") (class "Default")
      (node (ref "ARDUINO_DUE1") (pin "13") (pinfunction "13_13") (pintype "bidirectional"))
    )
    (net (code "80") (name "unconnected-(ARDUINO_DUE1-Pad22)") (class "Default")
      (node (ref "ARDUINO_DUE1") (pin "22") (pinfunction "22_22") (pintype "bidirectional"))
    )
    (net (code "81") (name "unconnected-(ARDUINO_DUE1-Pad23)") (class "Default")
      (node (ref "ARDUINO_DUE1") (pin "23") (pinfunction "23_23") (pintype "bidirectional"))
    )
    (net (code "82") (name "unconnected-(ARDUINO_DUE1-Pad24)") (class "Default")
      (node (ref "ARDUINO_DUE1") (pin "24") (pinfunction "24_24") (pintype "bidirectional"))
    )
    (net (code "83") (name "unconnected-(ARDUINO_DUE1-Pad25)") (class "Default")
      (node (ref "ARDUINO_DUE1") (pin "25") (pinfunction "25_25") (pintype "bidirectional"))
    )
    (net (code "84") (name "unconnected-(ARDUINO_DUE1-Pad26)") (class "Default")
      (node (ref "ARDUINO_DUE1") (pin "26") (pinfunction "26_26") (pintype "bidirectional"))
    )
    (net (code "85") (name "unconnected-(ARDUINO_DUE1-Pad27)") (class "Default")
      (node (ref "ARDUINO_DUE1") (pin "27") (pinfunction "27_27") (pintype "bidirectional"))
    )
    (net (code "86") (name "unconnected-(ARDUINO_DUE1-Pad28)") (class "Default")
      (node (ref "ARDUINO_DUE1") (pin "28") (pinfunction "28_28") (pintype "bidirectional"))
    )
    (net (code "87") (name "unconnected-(ARDUINO_DUE1-Pad29)") (class "Default")
      (node (ref "ARDUINO_DUE1") (pin "29") (pinfunction "29_29") (pintype "bidirectional"))
    )
    (net (code "88") (name "unconnected-(ARDUINO_DUE1-Pad30)") (class "Default")
      (node (ref "ARDUINO_DUE1") (pin "30") (pinfunction "30_30") (pintype "bidirectional"))
    )
    (net (code "89") (name "unconnected-(ARDUINO_DUE1-Pad31)") (class "Default")
      (node (ref "ARDUINO_DUE1") (pin "31") (pinfunction "31_31") (pintype "bidirectional"))
    )
    (net (code "90") (name "unconnected-(ARDUINO_DUE1-Pad32)") (class "Default")
      (node (ref "ARDUINO_DUE1") (pin "32") (pinfunction "32_32") (pintype "bidirectional"))
    )
    (net (code "91") (name "unconnected-(ARDUINO_DUE1-Pad41)") (class "Default")
      (node (ref "ARDUINO_DUE1") (pin "41") (pinfunction "41_41") (pintype "bidirectional"))
    )
    (net (code "92") (name "unconnected-(ARDUINO_DUE1-Pad42)") (class "Default")
      (node (ref "ARDUINO_DUE1") (pin "42") (pinfunction "42_42") (pintype "bidirectional"))
    )
    (net (code "93") (name "unconnected-(ARDUINO_DUE1-Pad43)") (class "Default")
      (node (ref "ARDUINO_DUE1") (pin "43") (pinfunction "43_43") (pintype "bidirectional"))
    )
    (net (code "94") (name "unconnected-(ARDUINO_DUE1-Pad52)") (class "Default")
      (node (ref "ARDUINO_DUE1") (pin "52") (pinfunction "52_52") (pintype "bidirectional"))
    )
    (net (code "95") (name "unconnected-(ARDUINO_DUE1-Pad53)") (class "Default")
      (node (ref "ARDUINO_DUE1") (pin "53") (pinfunction "53_53") (pintype "bidirectional"))
    )
    (net (code "96") (name "unconnected-(ARDUINO_DUE1-PadAREF)") (class "Default")
      (node (ref "ARDUINO_DUE1") (pin "AREF") (pinfunction "AREF_AREF") (pintype "bidirectional"))
    )
    (net (code "97") (name "unconnected-(ARDUINO_DUE1-PadDAC0)") (class "Default")
      (node (ref "ARDUINO_DUE1") (pin "DAC0") (pinfunction "DAC0_DAC0") (pintype "bidirectional"))
    )
    (net (code "98") (name "unconnected-(ARDUINO_DUE1-PadDAC1)") (class "Default")
      (node (ref "ARDUINO_DUE1") (pin "DAC1") (pinfunction "DAC1_DAC1") (pintype "bidirectional"))
    )
    (net (code "99") (name "unconnected-(ARDUINO_DUE1-PadGND_ICSP1)") (class "Default")
      (node (ref "ARDUINO_DUE1") (pin "GND_ICSP1") (pinfunction "GND_ICSP1_GND_ICSP1") (pintype "bidirectional"))
    )
    (net (code "100") (name "unconnected-(ARDUINO_DUE1-PadIOREF)") (class "Default")
      (node (ref "ARDUINO_DUE1") (pin "IOREF") (pinfunction "IOREF_IOREF") (pintype "bidirectional"))
    )
    (net (code "101") (name "unconnected-(ARDUINO_DUE1-PadJTAG_RESET)") (class "Default")
      (node (ref "ARDUINO_DUE1") (pin "JTAG_RESET") (pinfunction "JTAG_RESET_JTAG_RESET") (pintype "bidirectional"))
    )
    (net (code "102") (name "unconnected-(ARDUINO_DUE1-PadJTAG_TCK)") (class "Default")
      (node (ref "ARDUINO_DUE1") (pin "JTAG_TCK") (pinfunction "JTAG_TCK_JTAG_TCK") (pintype "bidirectional"))
    )
    (net (code "103") (name "unconnected-(ARDUINO_DUE1-PadJTAG_TCK_2)") (class "Default")
      (node (ref "ARDUINO_DUE1") (pin "JTAG_TCK_2") (pinfunction "JTAG_TCK_2_JTAG_TCK_2") (pintype "bidirectional"))
    )
    (net (code "104") (name "unconnected-(ARDUINO_DUE1-PadJTAG_TDI)") (class "Default")
      (node (ref "ARDUINO_DUE1") (pin "JTAG_TDI") (pinfunction "JTAG_TDI_JTAG_TDI") (pintype "bidirectional"))
    )
    (net (code "105") (name "unconnected-(ARDUINO_DUE1-PadJTAG_TDO)") (class "Default")
      (node (ref "ARDUINO_DUE1") (pin "JTAG_TDO") (pinfunction "JTAG_TDO_JTAG_TDO") (pintype "bidirectional"))
    )
    (net (code "106") (name "unconnected-(ARDUINO_DUE1-PadJTAG_TMS)") (class "Default")
      (node (ref "ARDUINO_DUE1") (pin "JTAG_TMS") (pinfunction "JTAG_TMS_JTAG_TMS") (pintype "bidirectional"))
    )
    (net (code "107") (name "unconnected-(ARDUINO_DUE1-PadJTAG_TMS_2)") (class "Default")
      (node (ref "ARDUINO_DUE1") (pin "JTAG_TMS_2") (pinfunction "JTAG_TMS_2_JTAG_TMS_2") (pintype "bidirectional"))
    )
    (net (code "108") (name "unconnected-(ARDUINO_DUE1-PadMISO)") (class "Default")
      (node (ref "ARDUINO_DUE1") (pin "MISO") (pinfunction "MISO_MISO") (pintype "bidirectional"))
    )
    (net (code "109") (name "unconnected-(ARDUINO_DUE1-PadMISO2)") (class "Default")
      (node (ref "ARDUINO_DUE1") (pin "MISO2") (pinfunction "MISO2_MISO2") (pintype "bidirectional"))
    )
    (net (code "110") (name "unconnected-(ARDUINO_DUE1-PadMOSI)") (class "Default")
      (node (ref "ARDUINO_DUE1") (pin "MOSI") (pinfunction "MOSI_MOSI") (pintype "bidirectional"))
    )
    (net (code "111") (name "unconnected-(ARDUINO_DUE1-PadMOSI2)") (class "Default")
      (node (ref "ARDUINO_DUE1") (pin "MOSI2") (pinfunction "MOSI2_MOSI2") (pintype "bidirectional"))
    )
    (net (code "112") (name "unconnected-(ARDUINO_DUE1-PadRESET)") (class "Default")
      (node (ref "ARDUINO_DUE1") (pin "RESET") (pinfunction "RESET_RESET") (pintype "bidirectional"))
    )
    (net (code "113") (name "unconnected-(ARDUINO_DUE1-PadRESET2)") (class "Default")
      (node (ref "ARDUINO_DUE1") (pin "RESET2") (pinfunction "RESET2_RESET2") (pintype "bidirectional"))
    )
    (net (code "114") (name "unconnected-(ARDUINO_DUE1-PadSCK2)") (class "Default")
      (node (ref "ARDUINO_DUE1") (pin "SCK2") (pinfunction "SCK2_SCK2") (pintype "bidirectional"))
    )
    (net (code "115") (name "unconnected-(ARDUINO_DUE1-PadSCL1)") (class "Default")
      (node (ref "ARDUINO_DUE1") (pin "SCL1") (pinfunction "SCL1_SCL1") (pintype "bidirectional"))
    )
    (net (code "116") (name "unconnected-(ARDUINO_DUE1-PadSDA1)") (class "Default")
      (node (ref "ARDUINO_DUE1") (pin "SDA1") (pinfunction "SDA1_SDA1") (pintype "bidirectional"))
    )
    (net (code "117") (name "unconnected-(ARDUINO_DUE1-PadSPCK)") (class "Default")
      (node (ref "ARDUINO_DUE1") (pin "SPCK") (pinfunction "SPCK_SPCK") (pintype "bidirectional"))
    )
    (net (code "118") (name "unconnected-(ARDUINO_DUE1-PadVIN)") (class "Default")
      (node (ref "ARDUINO_DUE1") (pin "VIN") (pinfunction "VIN_VIN") (pintype "bidirectional"))
    )
    (net (code "119") (name "unconnected-(ARDUINO_DUE1-RX0<0-Pad0)") (class "Default")
      (node (ref "ARDUINO_DUE1") (pin "0") (pinfunction "RX0<0_0") (pintype "bidirectional"))
    )
    (net (code "120") (name "unconnected-(ARDUINO_DUE1-RX1_19-Pad19)") (class "Default")
      (node (ref "ARDUINO_DUE1") (pin "19") (pinfunction "RX1_19_19") (pintype "bidirectional"))
    )
    (net (code "121") (name "unconnected-(ARDUINO_DUE1-RX2_17-Pad17)") (class "Default")
      (node (ref "ARDUINO_DUE1") (pin "17") (pinfunction "RX2_17_17") (pintype "bidirectional"))
    )
    (net (code "122") (name "unconnected-(ARDUINO_DUE1-RX3_15-Pad15)") (class "Default")
      (node (ref "ARDUINO_DUE1") (pin "15") (pinfunction "RX3_15_15") (pintype "bidirectional"))
    )
    (net (code "123") (name "unconnected-(ARDUINO_DUE1-SCL_21-Pad21)") (class "Default")
      (node (ref "ARDUINO_DUE1") (pin "21") (pinfunction "SCL_21_21") (pintype "bidirectional"))
    )
    (net (code "124") (name "unconnected-(ARDUINO_DUE1-SDA_20-Pad20)") (class "Default")
      (node (ref "ARDUINO_DUE1") (pin "20") (pinfunction "SDA_20_20") (pintype "bidirectional"))
    )
    (net (code "125") (name "unconnected-(ARDUINO_DUE1-TX0>1-Pad1)") (class "Default")
      (node (ref "ARDUINO_DUE1") (pin "1") (pinfunction "TX0>1_1") (pintype "bidirectional"))
    )
    (net (code "126") (name "unconnected-(ARDUINO_DUE1-TX1_18-Pad18)") (class "Default")
      (node (ref "ARDUINO_DUE1") (pin "18") (pinfunction "TX1_18_18") (pintype "bidirectional"))
    )
    (net (code "127") (name "unconnected-(ARDUINO_DUE1-TX2_16-Pad16)") (class "Default")
      (node (ref "ARDUINO_DUE1") (pin "16") (pinfunction "TX2_16_16") (pintype "bidirectional"))
    )
    (net (code "128") (name "unconnected-(ARDUINO_DUE1-TX3_14-Pad14)") (class "Default")
      (node (ref "ARDUINO_DUE1") (pin "14") (pinfunction "TX3_14_14") (pintype "bidirectional"))
    )
    (net (code "129") (name "unconnected-(IC2-ON1-Pad1)") (class "Default")
      (node (ref "IC2") (pin "1") (pinfunction "ON1_1") (pintype "passive"))
    )
    (net (code "130") (name "unconnected-(IC2-ON2-Pad5)") (class "Default")
      (node (ref "IC2") (pin "5") (pinfunction "ON2_5") (pintype "passive"))
    )
    (net (code "131") (name "unconnected-(IC2-OPT-Pad8)") (class "Default")
      (node (ref "IC2") (pin "8") (pinfunction "OPT_8") (pintype "passive"))
    )
    (net (code "132") (name "unconnected-(IC4-ON1-Pad1)") (class "Default")
      (node (ref "IC4") (pin "1") (pinfunction "ON1_1") (pintype "passive"))
    )
    (net (code "133") (name "unconnected-(IC4-ON2-Pad5)") (class "Default")
      (node (ref "IC4") (pin "5") (pinfunction "ON2_5") (pintype "passive"))
    )
    (net (code "134") (name "unconnected-(IC4-OPT-Pad8)") (class "Default")
      (node (ref "IC4") (pin "8") (pinfunction "OPT_8") (pintype "passive"))
    )
    (net (code "135") (name "unconnected-(V1C-B8-Pad11)") (class "Default")
      (node (ref "V1") (pin "11") (pinfunction "B8_11") (pintype "bidirectional"))
    )
  )
)
